# Schematic.net
KiCad netlist of a schematic drawn in EAGLE
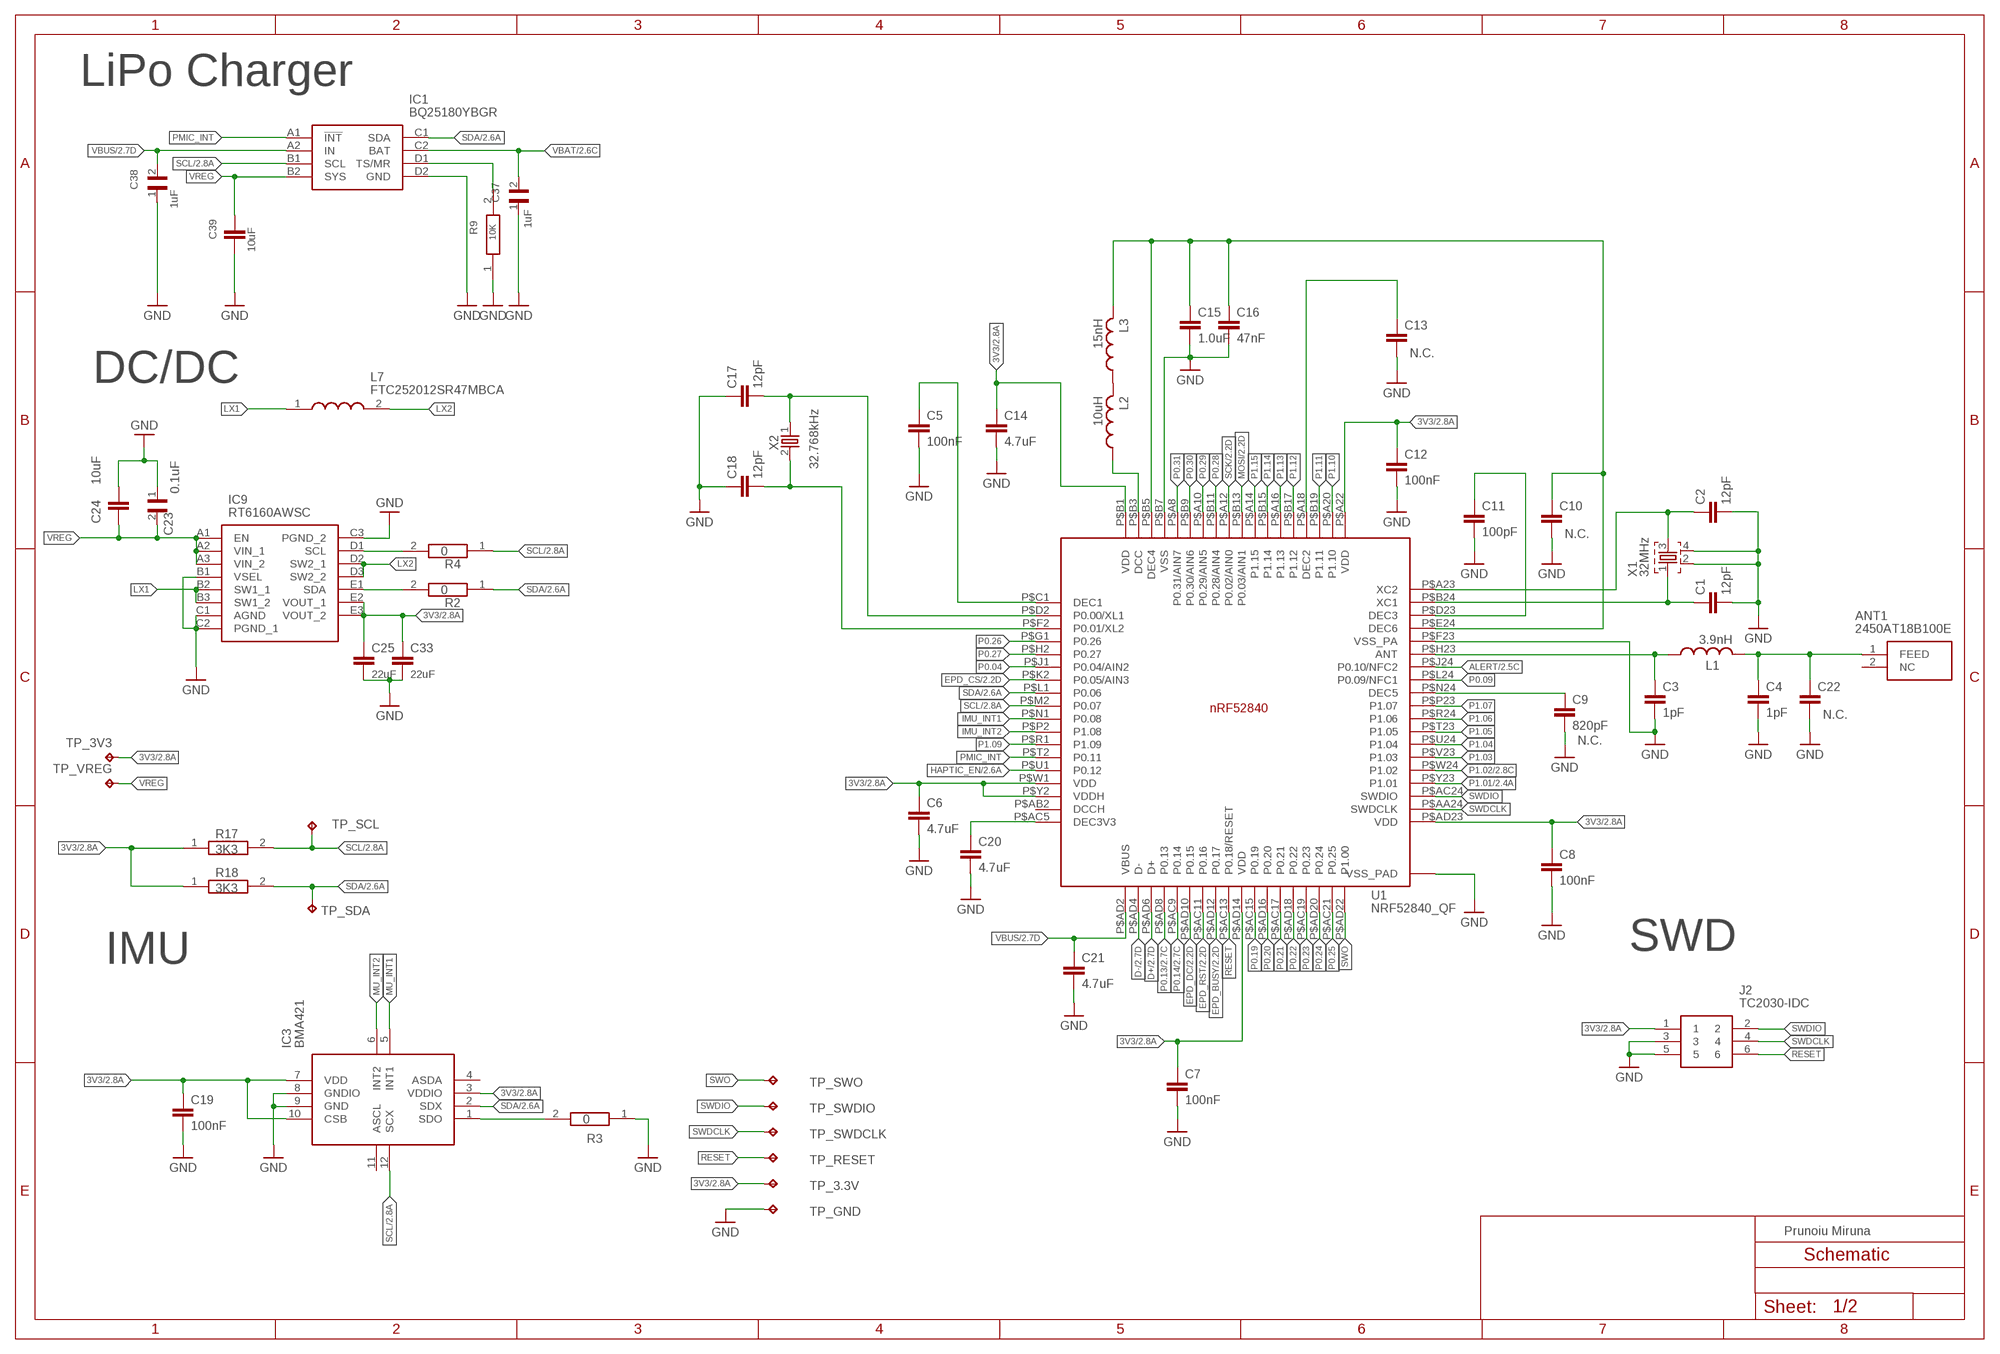
[diagram p0: schematic, sheet 1]
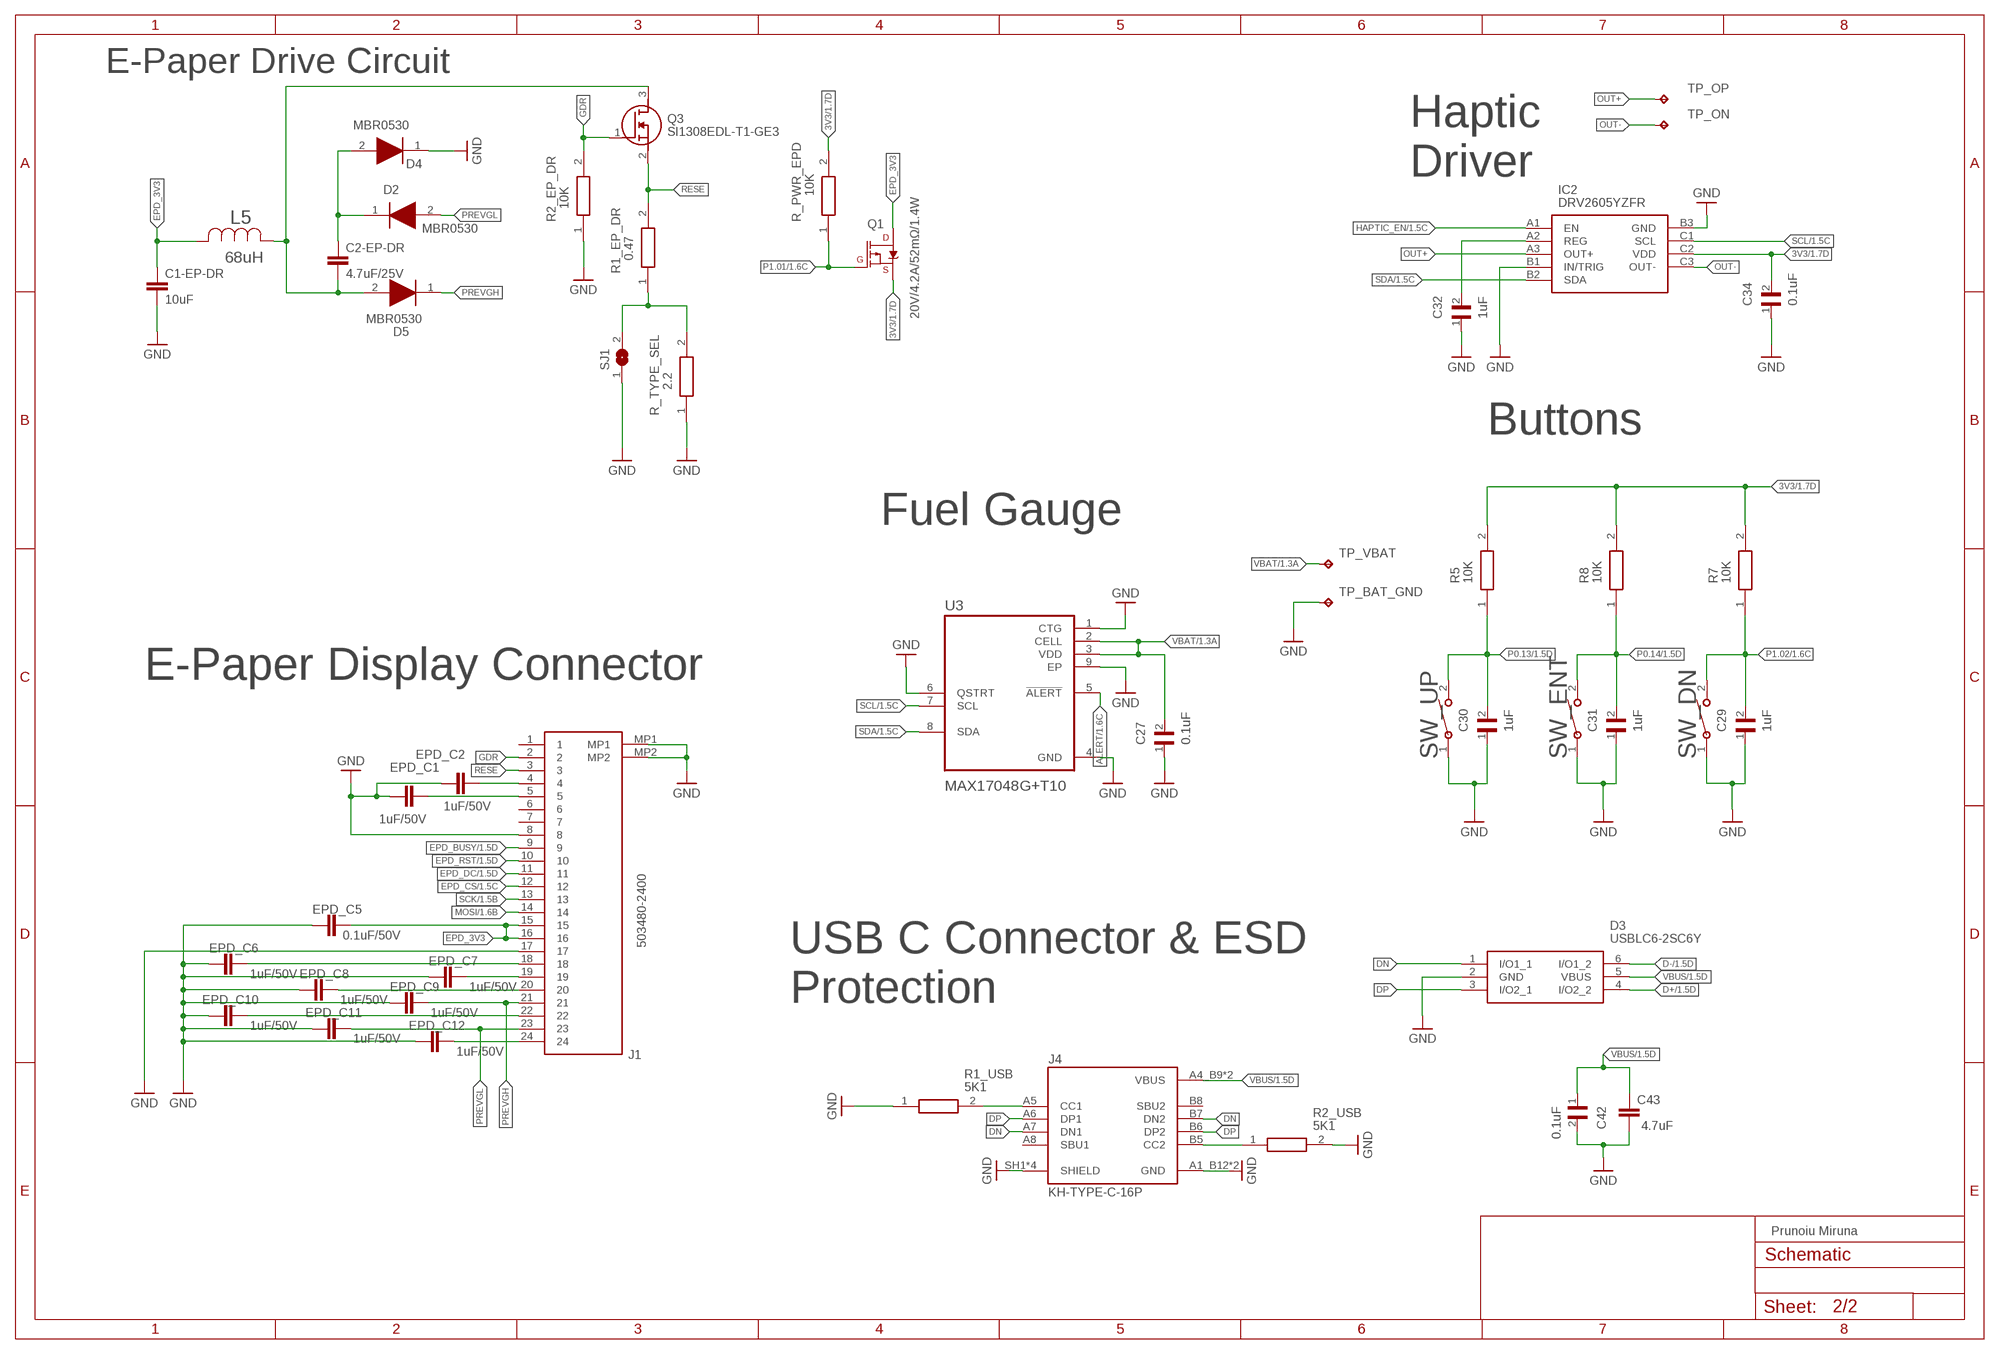
[diagram p1: schematic, sheet 2]

(export (version "E")
  (design (tool "Eeschema 10.0.6"))
  (components
    (comp (ref "C1-EP-DR")
      (value "10uF")
      (footprint "eagle-import:NORDIC_NRF_3_RESC0201_L")
      (libsource (lib "eagle-import") (part "InkTime_v5_vf.CHkS0jDyTK2MUtA_sH1VBA_NORDIC_NRF_3_CAPACITOR_0201_L"))
    )
    (comp (ref "C2-EP-DR")
      (value "4.7uF/25V")
      (footprint "eagle-import:NORDIC_NRF_3_RESC0201_L")
      (libsource (lib "eagle-import") (part "InkTime_v5_vf.CHkS0jDyTK2MUtA_sH1VBA_NORDIC_NRF_3_CAPACITOR_0201_L"))
    )
    (comp (ref "C27")
      (value "0.1uF")
      (footprint "eagle-import:GRM011R60J152KE01L_2_CAPC0201X13N")
      (fields (field (name "MF") "Murata") (field (name "MP") "GRM011R60J152KE01L"))
      (libsource (lib "eagle-import") (part "GRM011R60J152KE01L_2_GRM011R60J152KE01L"))
    )
    (comp (ref "C29")
      (value "1uF")
      (footprint "eagle-import:GRM011R60J152KE01L_2_CAPC0201X13N")
      (fields (field (name "MF") "Murata") (field (name "MP") "GRM011R60J152KE01L"))
      (libsource (lib "eagle-import") (part "GRM011R60J152KE01L_2_GRM011R60J152KE01L"))
    )
    (comp (ref "C30")
      (value "1uF")
      (footprint "eagle-import:GRM011R60J152KE01L_2_CAPC0201X13N")
      (fields (field (name "MF") "Murata") (field (name "MP") "GRM011R60J152KE01L"))
      (libsource (lib "eagle-import") (part "GRM011R60J152KE01L_2_GRM011R60J152KE01L"))
    )
    (comp (ref "C31")
      (value "1uF")
      (footprint "eagle-import:GRM011R60J152KE01L_2_CAPC0201X13N")
      (fields (field (name "MF") "Murata") (field (name "MP") "GRM011R60J152KE01L"))
      (libsource (lib "eagle-import") (part "GRM011R60J152KE01L_2_GRM011R60J152KE01L"))
    )
    (comp (ref "C32")
      (value "1uF")
      (footprint "eagle-import:GRM011R60J152KE01L_2_CAPC0201X13N")
      (fields (field (name "MF") "Murata") (field (name "MP") "GRM011R60J152KE01L"))
      (libsource (lib "eagle-import") (part "GRM011R60J152KE01L_2_GRM011R60J152KE01L"))
    )
    (comp (ref "C34")
      (value "0.1uF")
      (footprint "eagle-import:GRM011R60J152KE01L_2_CAPC0201X13N")
      (fields (field (name "MF") "Murata") (field (name "MP") "GRM011R60J152KE01L"))
      (libsource (lib "eagle-import") (part "GRM011R60J152KE01L_2_GRM011R60J152KE01L"))
    )
    (comp (ref "C42")
      (value "0.1uF")
      (footprint "eagle-import:GRM011R60J152KE01L_2_CAPC0201X13N")
      (fields (field (name "MF") "Murata") (field (name "MP") "GRM011R60J152KE01L"))
      (libsource (lib "eagle-import") (part "GRM011R60J152KE01L_2_GRM011R60J152KE01L"))
    )
    (comp (ref "C43")
      (value "4.7uF")
      (footprint "eagle-import:NORDIC_NRF_3_RESC0201_L")
      (libsource (lib "eagle-import") (part "InkTime_v5_vf.CHkS0jDyTK2MUtA_sH1VBA_NORDIC_NRF_3_CAPACITOR_0201_L"))
    )
    (comp (ref "D2")
      (value "MBR0530")
      (footprint "eagle-import:ESP32_C6_LIBRARY_5_SOD3716X135N")
      (fields (field (name "MF") "ON Semiconductor"))
      (libsource (lib "eagle-import") (part "ESP32_C6_LIBRARY_5_MBR0530"))
    )
    (comp (ref "D3")
      (value "USBLC6-2SC6Y")
      (footprint "eagle-import:ESP32_C6_LIBRARY_3_SOT95P280X145-6N")
      (fields (field (name "MF") "STMicroelectronics"))
      (libsource (lib "eagle-import") (part "ESP32_C6_LIBRARY_3_USBLC6-2SC6Y"))
    )
    (comp (ref "D4")
      (value "MBR0530")
      (footprint "eagle-import:ESP32_C6_LIBRARY_5_SOD3716X135N")
      (fields (field (name "MF") "ON Semiconductor"))
      (libsource (lib "eagle-import") (part "ESP32_C6_LIBRARY_5_MBR0530"))
    )
    (comp (ref "D5")
      (value "MBR0530")
      (footprint "eagle-import:ESP32_C6_LIBRARY_5_SOD3716X135N")
      (fields (field (name "MF") "ON Semiconductor"))
      (libsource (lib "eagle-import") (part "ESP32_C6_LIBRARY_5_MBR0530"))
    )
    (comp (ref "EPD_C1")
      (value "1uF/50V")
      (footprint "eagle-import:NORDIC_NRF_3_RESC0201_L")
      (libsource (lib "eagle-import") (part "InkTime_v5_vf.CHkS0jDyTK2MUtA_sH1VBA_NORDIC_NRF_3_CAPACITOR_0201_L"))
    )
    (comp (ref "EPD_C2")
      (value "1uF/50V")
      (footprint "eagle-import:NORDIC_NRF_3_RESC0201_L")
      (libsource (lib "eagle-import") (part "InkTime_v5_vf.CHkS0jDyTK2MUtA_sH1VBA_NORDIC_NRF_3_CAPACITOR_0201_L"))
    )
    (comp (ref "EPD_C5")
      (value "0.1uF/50V")
      (footprint "eagle-import:NORDIC_NRF_3_RESC0201_L")
      (libsource (lib "eagle-import") (part "InkTime_v5_vf.CHkS0jDyTK2MUtA_sH1VBA_NORDIC_NRF_3_CAPACITOR_0201_L"))
    )
    (comp (ref "EPD_C6")
      (value "1uF/50V")
      (footprint "eagle-import:NORDIC_NRF_3_RESC0201_L")
      (libsource (lib "eagle-import") (part "InkTime_v5_vf.CHkS0jDyTK2MUtA_sH1VBA_NORDIC_NRF_3_CAPACITOR_0201_L"))
    )
    (comp (ref "EPD_C7")
      (value "1uF/50V")
      (footprint "eagle-import:NORDIC_NRF_3_RESC0201_L")
      (libsource (lib "eagle-import") (part "InkTime_v5_vf.CHkS0jDyTK2MUtA_sH1VBA_NORDIC_NRF_3_CAPACITOR_0201_L"))
    )
    (comp (ref "EPD_C8")
      (value "1uF/50V")
      (footprint "eagle-import:NORDIC_NRF_3_RESC0201_L")
      (libsource (lib "eagle-import") (part "InkTime_v5_vf.CHkS0jDyTK2MUtA_sH1VBA_NORDIC_NRF_3_CAPACITOR_0201_L"))
    )
    (comp (ref "EPD_C9")
      (value "1uF/50V")
      (footprint "eagle-import:NORDIC_NRF_3_RESC0201_L")
      (libsource (lib "eagle-import") (part "InkTime_v5_vf.CHkS0jDyTK2MUtA_sH1VBA_NORDIC_NRF_3_CAPACITOR_0201_L"))
    )
    (comp (ref "EPD_C10")
      (value "1uF/50V")
      (footprint "eagle-import:NORDIC_NRF_3_RESC0201_L")
      (libsource (lib "eagle-import") (part "InkTime_v5_vf.CHkS0jDyTK2MUtA_sH1VBA_NORDIC_NRF_3_CAPACITOR_0201_L"))
    )
    (comp (ref "EPD_C11")
      (value "1uF/50V")
      (footprint "eagle-import:NORDIC_NRF_3_RESC0201_L")
      (libsource (lib "eagle-import") (part "InkTime_v5_vf.CHkS0jDyTK2MUtA_sH1VBA_NORDIC_NRF_3_CAPACITOR_0201_L"))
    )
    (comp (ref "EPD_C12")
      (value "1uF/50V")
      (footprint "eagle-import:NORDIC_NRF_3_RESC0201_L")
      (libsource (lib "eagle-import") (part "InkTime_v5_vf.CHkS0jDyTK2MUtA_sH1VBA_NORDIC_NRF_3_CAPACITOR_0201_L"))
    )
    (comp (ref "IC2")
      (value "DRV2605YZFR")
      (footprint "eagle-import:DRV2605YZFR_BGA9C50P3X3_144X144X62")
      (libsource (lib "eagle-import") (part "DRV2605YZFR_DRV2605YZFR"))
    )
    (comp (ref "J1")
      (value "503480-2400")
      (footprint "eagle-import:503480-2400_5034802400")
      (fields (field (name "MOUSER_PART_NUMBER") "538-503480-2400"))
      (libsource (lib "eagle-import") (part "503480-2400_503480-2400"))
    )
    (comp (ref "J4")
      (value "KH-TYPE-C-16P")
      (footprint "eagle-import:KH-TYPE-C-16P_KINGHELM_KH-TYPE-C-16P")
      (fields (field (name "MF") "kinghelm"))
      (libsource (lib "eagle-import") (part "KH-TYPE-C-16P_KH-TYPE-C-16P"))
    )
    (comp (ref "L5")
      (value "68uH")
      (footprint "eagle-import:ESP32_C6_LIBRARY_2_IND_4828-WE-TPC_WRE")
      (fields
        (field (name "MANUFACTURER_PART_NUMBER") "744043680")
        (field (name "COPYRIGHT") "Copyright (C) 2024 Ultra Librarian. All rights reserved.")
      )
      (libsource (lib "eagle-import") (part "ESP32_C6_LIBRARY_2_744043680IND_4828-WE-TPC_WRE"))
    )
    (comp (ref "Q1")
      (value "20V/4.2A/52mΩ/1.4W")
      (footprint "eagle-import:ESP32_C6_LIBRARY_4_ESP32_C6_LIBRARY_4_ESP32_C6_LIBRARY_4_ESP32_C6_LIBRARY_4_ESP32_WROVER_SPARKFUN-DISCRETESEMI_SOT23-3")
      (libsource (lib "eagle-import") (part "ESP32_C6_LIBRARY_4_ESP32_WROVER_SPARKFUN-DISCRETESEMI_MOSFET_PCH-DMG2305UX-7"))
    )
    (comp (ref "Q3")
      (value "SI1308EDL-T1-GE3")
      (footprint "eagle-import:ESP32_C6_LIBRARY_6_SOT65P210X110-3N")
      (fields (field (name "MF") "Vishay Siliconix"))
      (libsource (lib "eagle-import") (part "ESP32_C6_LIBRARY_6_SI1308EDL-T1-GE3"))
    )
    (comp (ref "R1_EP_DR")
      (value "0.47")
      (footprint "eagle-import:CPF0201D7K68C1_0201")
      (libsource (lib "eagle-import") (part "InkTime_v5_vf.CHkS0jDyTK2MUtA_sH1VBA_CPF0201D7K68C1_CPF0201D7K68C1"))
    )
    (comp (ref "R1_USB")
      (value "5K1")
      (footprint "eagle-import:CPF0201D7K68C1_0201")
      (libsource (lib "eagle-import") (part "InkTime_v5_vf.CHkS0jDyTK2MUtA_sH1VBA_CPF0201D7K68C1_CPF0201D7K68C1"))
    )
    (comp (ref "R2_EP_DR")
      (value "10K")
      (footprint "eagle-import:CPF0201D7K68C1_0201")
      (libsource (lib "eagle-import") (part "InkTime_v5_vf.CHkS0jDyTK2MUtA_sH1VBA_CPF0201D7K68C1_CPF0201D7K68C1"))
    )
    (comp (ref "R2_USB")
      (value "5K1")
      (footprint "eagle-import:CPF0201D7K68C1_0201")
      (libsource (lib "eagle-import") (part "InkTime_v5_vf.CHkS0jDyTK2MUtA_sH1VBA_CPF0201D7K68C1_CPF0201D7K68C1"))
    )
    (comp (ref "R5")
      (value "10K")
      (footprint "eagle-import:CPF0201D7K68C1_0201")
      (libsource (lib "eagle-import") (part "InkTime_v5_vf.CHkS0jDyTK2MUtA_sH1VBA_CPF0201D7K68C1_CPF0201D7K68C1"))
    )
    (comp (ref "R7")
      (value "10K")
      (footprint "eagle-import:CPF0201D7K68C1_0201")
      (libsource (lib "eagle-import") (part "InkTime_v5_vf.CHkS0jDyTK2MUtA_sH1VBA_CPF0201D7K68C1_CPF0201D7K68C1"))
    )
    (comp (ref "R8")
      (value "10K")
      (footprint "eagle-import:CPF0201D7K68C1_0201")
      (libsource (lib "eagle-import") (part "InkTime_v5_vf.CHkS0jDyTK2MUtA_sH1VBA_CPF0201D7K68C1_CPF0201D7K68C1"))
    )
    (comp (ref "R_PWR_EPD")
      (value "10K")
      (footprint "eagle-import:CPF0201D7K68C1_0201")
      (libsource (lib "eagle-import") (part "InkTime_v5_vf.CHkS0jDyTK2MUtA_sH1VBA_CPF0201D7K68C1_CPF0201D7K68C1"))
    )
    (comp (ref "R_TYPE_SEL")
      (value "2.2")
      (footprint "eagle-import:CPF0201D7K68C1_0201")
      (libsource (lib "eagle-import") (part "InkTime_v5_vf.CHkS0jDyTK2MUtA_sH1VBA_CPF0201D7K68C1_CPF0201D7K68C1"))
    )
    (comp (ref "SJ1")
      (value "ESP32_C6_LIBRARY_7_JUMPER_SJ")
      (footprint "eagle-import:ESP32_C6_LIBRARY_7_JUMPER_SJ")
      (libsource (lib "eagle-import") (part "ESP32_C6_LIBRARY_7_JUMPER_SJ"))
    )
    (comp (ref "SW_DN")
      (value "2025-10-22_07-23-44_LIBRARY_EVP-AKE31ASW_EVP-AKE31A_PAN")
      (footprint "eagle-import:2025-10-22_07-23-44_LIBRARY_SW_EVP-AKE31A_PAN")
      (fields
        (field (name "MANUFACTURER_PART_NUMBER") "EVP-AKE31A")
        (field (name "COPYRIGHT") "Copyright (C) 2025 Ultra Librarian. All rights reserved.")
      )
      (libsource (lib "eagle-import") (part "2025-10-22_07-23-44_LIBRARY_EVP-AKE31ASW_EVP-AKE31A_PAN"))
    )
    (comp (ref "SW_ENT")
      (value "2025-10-22_07-23-44_LIBRARY_EVP-AKE31ASW_EVP-AKE31A_PAN")
      (footprint "eagle-import:2025-10-22_07-23-44_LIBRARY_SW_EVP-AKE31A_PAN")
      (fields
        (field (name "MANUFACTURER_PART_NUMBER") "EVP-AKE31A")
        (field (name "COPYRIGHT") "Copyright (C) 2025 Ultra Librarian. All rights reserved.")
      )
      (libsource (lib "eagle-import") (part "2025-10-22_07-23-44_LIBRARY_EVP-AKE31ASW_EVP-AKE31A_PAN"))
    )
    (comp (ref "SW_UP")
      (value "2025-10-22_07-23-44_LIBRARY_EVP-AKE31ASW_EVP-AKE31A_PAN")
      (footprint "eagle-import:2025-10-22_07-23-44_LIBRARY_SW_EVP-AKE31A_PAN")
      (fields
        (field (name "MANUFACTURER_PART_NUMBER") "EVP-AKE31A")
        (field (name "COPYRIGHT") "Copyright (C) 2025 Ultra Librarian. All rights reserved.")
      )
      (libsource (lib "eagle-import") (part "2025-10-22_07-23-44_LIBRARY_EVP-AKE31ASW_EVP-AKE31A_PAN"))
    )
    (comp (ref "TP_BAT_GND")
      (value "HECTOR_WATCH_1_TPTP20R")
      (footprint "eagle-import:HECTOR_WATCH_1_TP20R")
      (libsource (lib "eagle-import") (part "InkTime_v5_vf.CHkS0jDyTK2MUtA_sH1VBA_HECTOR_WATCH_1_TPTP20R"))
    )
    (comp (ref "TP_ON")
      (value "HECTOR_WATCH_1_TPTP20R")
      (footprint "eagle-import:HECTOR_WATCH_1_TP20R")
      (libsource (lib "eagle-import") (part "InkTime_v5_vf.CHkS0jDyTK2MUtA_sH1VBA_HECTOR_WATCH_1_TPTP20R"))
    )
    (comp (ref "TP_OP")
      (value "HECTOR_WATCH_1_TPTP20R")
      (footprint "eagle-import:HECTOR_WATCH_1_TP20R")
      (libsource (lib "eagle-import") (part "InkTime_v5_vf.CHkS0jDyTK2MUtA_sH1VBA_HECTOR_WATCH_1_TPTP20R"))
    )
    (comp (ref "TP_VBAT")
      (value "HECTOR_WATCH_1_TPTP20R")
      (footprint "eagle-import:HECTOR_WATCH_1_TP20R")
      (libsource (lib "eagle-import") (part "InkTime_v5_vf.CHkS0jDyTK2MUtA_sH1VBA_HECTOR_WATCH_1_TPTP20R"))
    )
    (comp (ref "U3")
      (value "MAX17048G+T10")
      (footprint "eagle-import:ESP32_C6_LIBRARY_SON50P200X200X80-9N")
      (fields (field (name "MF") "Analog Devices"))
      (libsource (lib "eagle-import") (part "ESP32_C6_LIBRARY_MAX17048G+T10"))
    )
    (comp (ref "ANT1")
      (value "2450AT18B100E")
      (footprint "eagle-import:2450AT18B100E_ANTC3216X140N")
      (fields (field (name "MOUSER_PART_NUMBER") "609-2450AT18B100E"))
      (libsource (lib "eagle-import") (part "2450AT18B100E_2450AT18B100E"))
    )
    (comp (ref "C1")
      (value "12pF")
      (footprint "eagle-import:NORDIC_NRF_3_RESC0201_L")
      (libsource (lib "eagle-import") (part "InkTime_v5_vf.CHkS0jDyTK2MUtA_sH1VBA_NORDIC_NRF_3_CAPACITOR_0201_L"))
    )
    (comp (ref "C2")
      (value "12pF")
      (footprint "eagle-import:NORDIC_NRF_3_RESC0201_L")
      (libsource (lib "eagle-import") (part "InkTime_v5_vf.CHkS0jDyTK2MUtA_sH1VBA_NORDIC_NRF_3_CAPACITOR_0201_L"))
    )
    (comp (ref "C3")
      (value "1pF")
      (footprint "eagle-import:NORDIC_NRF_3_RESC0201_L")
      (libsource (lib "eagle-import") (part "InkTime_v5_vf.CHkS0jDyTK2MUtA_sH1VBA_NORDIC_NRF_3_CAPACITOR_0201_L"))
    )
    (comp (ref "C4")
      (value "1pF")
      (footprint "eagle-import:NORDIC_NRF_3_RESC0201_L")
      (libsource (lib "eagle-import") (part "InkTime_v5_vf.CHkS0jDyTK2MUtA_sH1VBA_NORDIC_NRF_3_CAPACITOR_0201_L"))
    )
    (comp (ref "C5")
      (value "100nF")
      (footprint "eagle-import:NORDIC_NRF_3_RESC0201_L")
      (libsource (lib "eagle-import") (part "InkTime_v5_vf.CHkS0jDyTK2MUtA_sH1VBA_NORDIC_NRF_3_CAPACITOR_0201_L"))
    )
    (comp (ref "C6")
      (value "4.7uF")
      (footprint "eagle-import:NORDIC_NRF_3_RESC0201_L")
      (libsource (lib "eagle-import") (part "InkTime_v5_vf.CHkS0jDyTK2MUtA_sH1VBA_NORDIC_NRF_3_CAPACITOR_0201_L"))
    )
    (comp (ref "C7")
      (value "100nF")
      (footprint "eagle-import:NORDIC_NRF_3_RESC0201_L")
      (libsource (lib "eagle-import") (part "InkTime_v5_vf.CHkS0jDyTK2MUtA_sH1VBA_NORDIC_NRF_3_CAPACITOR_0201_L"))
    )
    (comp (ref "C8")
      (value "100nF")
      (footprint "eagle-import:NORDIC_NRF_3_RESC0201_L")
      (libsource (lib "eagle-import") (part "InkTime_v5_vf.CHkS0jDyTK2MUtA_sH1VBA_NORDIC_NRF_3_CAPACITOR_0201_L"))
    )
    (comp (ref "C9")
      (value "820pF")
      (footprint "eagle-import:NORDIC_NRF_3_RESC0201_L")
      (fields (field (name "MAXTEMP") "N.C."))
      (libsource (lib "eagle-import") (part "InkTime_v5_vf.CHkS0jDyTK2MUtA_sH1VBA_NORDIC_NRF_3_CAPACITOR_0201_L"))
    )
    (comp (ref "C10")
      (value "NORDIC_NRF_3_CAPACITOR_0201_L")
      (footprint "eagle-import:NORDIC_NRF_3_RESC0201_L")
      (fields (field (name "MAXTEMP") "N.C."))
      (libsource (lib "eagle-import") (part "InkTime_v5_vf.CHkS0jDyTK2MUtA_sH1VBA_NORDIC_NRF_3_CAPACITOR_0201_L"))
    )
    (comp (ref "C11")
      (value "100pF")
      (footprint "eagle-import:NORDIC_NRF_3_RESC0201_L")
      (libsource (lib "eagle-import") (part "InkTime_v5_vf.CHkS0jDyTK2MUtA_sH1VBA_NORDIC_NRF_3_CAPACITOR_0201_L"))
    )
    (comp (ref "C12")
      (value "100nF")
      (footprint "eagle-import:NORDIC_NRF_3_RESC0201_L")
      (libsource (lib "eagle-import") (part "InkTime_v5_vf.CHkS0jDyTK2MUtA_sH1VBA_NORDIC_NRF_3_CAPACITOR_0201_L"))
    )
    (comp (ref "C13")
      (value "NORDIC_NRF_3_CAPACITOR_0201_L")
      (footprint "eagle-import:NORDIC_NRF_3_RESC0201_L")
      (fields (field (name "MAXTEMP") "N.C."))
      (libsource (lib "eagle-import") (part "InkTime_v5_vf.CHkS0jDyTK2MUtA_sH1VBA_NORDIC_NRF_3_CAPACITOR_0201_L"))
    )
    (comp (ref "C14")
      (value "4.7uF")
      (footprint "eagle-import:NORDIC_NRF_3_RESC0201_L")
      (libsource (lib "eagle-import") (part "InkTime_v5_vf.CHkS0jDyTK2MUtA_sH1VBA_NORDIC_NRF_3_CAPACITOR_0201_L"))
    )
    (comp (ref "C15")
      (value "1.0uF")
      (footprint "eagle-import:NORDIC_NRF_3_RESC0201_L")
      (libsource (lib "eagle-import") (part "InkTime_v5_vf.CHkS0jDyTK2MUtA_sH1VBA_NORDIC_NRF_3_CAPACITOR_0201_L"))
    )
    (comp (ref "C16")
      (value "47nF")
      (footprint "eagle-import:NORDIC_NRF_3_RESC0201_L")
      (libsource (lib "eagle-import") (part "InkTime_v5_vf.CHkS0jDyTK2MUtA_sH1VBA_NORDIC_NRF_3_CAPACITOR_0201_L"))
    )
    (comp (ref "C17")
      (value "12pF")
      (footprint "eagle-import:NORDIC_NRF_3_RESC0201_L")
      (libsource (lib "eagle-import") (part "InkTime_v5_vf.CHkS0jDyTK2MUtA_sH1VBA_NORDIC_NRF_3_CAPACITOR_0201_L"))
    )
    (comp (ref "C18")
      (value "12pF")
      (footprint "eagle-import:NORDIC_NRF_3_RESC0201_L")
      (libsource (lib "eagle-import") (part "InkTime_v5_vf.CHkS0jDyTK2MUtA_sH1VBA_NORDIC_NRF_3_CAPACITOR_0201_L"))
    )
    (comp (ref "C19")
      (value "100nF")
      (footprint "eagle-import:NORDIC_NRF_3_RESC0201_L")
      (libsource (lib "eagle-import") (part "NORDIC_NRF_3_CAPACITOR_0201_L"))
    )
    (comp (ref "C20")
      (value "4.7uF")
      (footprint "eagle-import:NORDIC_NRF_3_RESC0201_L")
      (libsource (lib "eagle-import") (part "InkTime_v5_vf.CHkS0jDyTK2MUtA_sH1VBA_NORDIC_NRF_3_CAPACITOR_0201_L"))
    )
    (comp (ref "C21")
      (value "4.7uF")
      (footprint "eagle-import:NORDIC_NRF_3_RESC0201_L")
      (libsource (lib "eagle-import") (part "InkTime_v5_vf.CHkS0jDyTK2MUtA_sH1VBA_NORDIC_NRF_3_CAPACITOR_0201_L"))
    )
    (comp (ref "C22")
      (value "NORDIC_NRF_3_CAPACITOR_0201_L")
      (footprint "eagle-import:NORDIC_NRF_3_RESC0201_L")
      (fields (field (name "MAXTEMP") "N.C."))
      (libsource (lib "eagle-import") (part "InkTime_v5_vf.CHkS0jDyTK2MUtA_sH1VBA_NORDIC_NRF_3_CAPACITOR_0201_L"))
    )
    (comp (ref "C23")
      (value "0.1uF")
      (footprint "eagle-import:GRM011R60J152KE01L_1_0201")
      (fields (field (name "VAL") "88"))
      (libsource (lib "eagle-import") (part "GRM011R60J152KE01L_1_GRM011R60J152KE01L"))
    )
    (comp (ref "C24")
      (value "10uF")
      (footprint "eagle-import:NORDIC_NRF_3_RESC0201_L")
      (libsource (lib "eagle-import") (part "NORDIC_NRF_3_CAPACITOR_0201_L"))
    )
    (comp (ref "C25")
      (value "22uF")
      (footprint "eagle-import:NORDIC_NRF_3_RESC0201_L")
      (libsource (lib "eagle-import") (part "NORDIC_NRF_3_CAPACITOR_0201_L"))
    )
    (comp (ref "C33")
      (value "22uF")
      (footprint "eagle-import:NORDIC_NRF_3_RESC0201_L")
      (libsource (lib "eagle-import") (part "NORDIC_NRF_3_CAPACITOR_0201_L"))
    )
    (comp (ref "C37")
      (value "1uF")
      (footprint "eagle-import:GRM011R60J152KE01L_1_0201")
      (libsource (lib "eagle-import") (part "GRM011R60J152KE01L_1_GRM011R60J152KE01L"))
    )
    (comp (ref "C38")
      (value "1uF")
      (footprint "eagle-import:GRM011R60J152KE01L_1_0201")
      (libsource (lib "eagle-import") (part "GRM011R60J152KE01L_1_GRM011R60J152KE01L"))
    )
    (comp (ref "C39")
      (value "10uF")
      (footprint "eagle-import:NORDIC_NRF_3_RESC0201_L")
      (libsource (lib "eagle-import") (part "NORDIC_NRF_3_CAPACITOR_0201_L"))
    )
    (comp (ref "IC1")
      (value "BQ25180YBGR")
      (footprint "eagle-import:BQ25180YBGR_BGA8C40P2X4_100X155X50")
      (fields (field (name "MOUSER_PART_NUMBER") "595-BQ25180YBGR"))
      (libsource (lib "eagle-import") (part "BQ25180YBGR_BQ25180YBGR"))
    )
    (comp (ref "IC3")
      (value "BMA421")
      (footprint "eagle-import:BMA423_BMA423")
      (fields (field (name "ARROW_PART_NUMBER") "BMA423") (field (name "MOUSER_PART_NUMBER") "262-BMA423"))
      (libsource (lib "eagle-import") (part "BMA423_BMA423"))
    )
    (comp (ref "IC9")
      (value "RT6160AWSC")
      (footprint "eagle-import:RT6160AWSC_BGA15C40P3X5_140X230X60")
      (fields (field (name "MOUSER_PART_NUMBER") "835-RT6160AWSC"))
      (libsource (lib "eagle-import") (part "RT6160AWSC_RT6160AWSC"))
    )
    (comp (ref "J2")
      (value "TC2030-IDC")
      (footprint "eagle-import:TC2030-IDC_TC2030IDC")
      (libsource (lib "eagle-import") (part "TC2030-IDC_TC2030-IDC"))
    )
    (comp (ref "L1")
      (value "3.9nH")
      (footprint "eagle-import:NORDIC_NRF_2_RESC0402_L")
      (libsource (lib "eagle-import") (part "NORDIC_NRF_2_INDUCTOR_0402_L"))
    )
    (comp (ref "L2")
      (value "10uH")
      (footprint "eagle-import:NORDIC_NRF_2_RESC0402_L")
      (libsource (lib "eagle-import") (part "NORDIC_NRF_2_INDUCTOR_0402_L"))
    )
    (comp (ref "L3")
      (value "15nH")
      (footprint "eagle-import:NORDIC_NRF_2_RESC0402_L")
      (libsource (lib "eagle-import") (part "NORDIC_NRF_2_INDUCTOR_0402_L"))
    )
    (comp (ref "L7")
      (value "FTC252012SR47MBCA")
      (footprint "eagle-import:MLP2016SR47MT0S1_INDC2016X100N")
      (libsource (lib "eagle-import") (part "MLP2016SR47MT0S1_FTC252012SR47MBCA"))
    )
    (comp (ref "R2")
      (value "0")
      (footprint "eagle-import:CPF0201D7K68C1_0201")
      (libsource (lib "eagle-import") (part "CPF0201D7K68C1_CPF0201D7K68C1"))
    )
    (comp (ref "R3")
      (value "0")
      (footprint "eagle-import:CPF0201D7K68C1_0201")
      (libsource (lib "eagle-import") (part "CPF0201D7K68C1_CPF0201D7K68C1"))
    )
    (comp (ref "R4")
      (value "0")
      (footprint "eagle-import:CPF0201D7K68C1_0201")
      (libsource (lib "eagle-import") (part "CPF0201D7K68C1_CPF0201D7K68C1"))
    )
    (comp (ref "R9")
      (value "10K")
      (footprint "eagle-import:CPF0201D7K68C1_0201")
      (libsource (lib "eagle-import") (part "CPF0201D7K68C1_CPF0201D7K68C1"))
    )
    (comp (ref "R17")
      (value "3K3")
      (footprint "eagle-import:CPF0201D7K68C1_0201")
      (libsource (lib "eagle-import") (part "CPF0201D7K68C1_CPF0201D7K68C1"))
    )
    (comp (ref "R18")
      (value "3K3")
      (footprint "eagle-import:CPF0201D7K68C1_0201")
      (libsource (lib "eagle-import") (part "CPF0201D7K68C1_CPF0201D7K68C1"))
    )
    (comp (ref "TP_3.3V")
      (value "HECTOR_WATCH_1_TPTP20R")
      (footprint "eagle-import:HECTOR_WATCH_1_TP20R")
      (libsource (lib "eagle-import") (part "HECTOR_WATCH_1_TPTP20R"))
    )
    (comp (ref "TP_3V3")
      (value "HECTOR_WATCH_1_TPTP20R")
      (footprint "eagle-import:HECTOR_WATCH_1_TP20R")
      (libsource (lib "eagle-import") (part "HECTOR_WATCH_1_TPTP20R"))
    )
    (comp (ref "TP_GND")
      (value "HECTOR_WATCH_1_TPTP20R")
      (footprint "eagle-import:HECTOR_WATCH_1_TP20R")
      (libsource (lib "eagle-import") (part "HECTOR_WATCH_1_TPTP20R"))
    )
    (comp (ref "TP_RESET")
      (value "HECTOR_WATCH_1_TPTP20R")
      (footprint "eagle-import:HECTOR_WATCH_1_TP20R")
      (libsource (lib "eagle-import") (part "HECTOR_WATCH_1_TPTP20R"))
    )
    (comp (ref "TP_SCL")
      (value "HECTOR_WATCH_1_TPTP20R")
      (footprint "eagle-import:HECTOR_WATCH_1_TP20R")
      (libsource (lib "eagle-import") (part "HECTOR_WATCH_1_TPTP20R"))
    )
    (comp (ref "TP_SDA")
      (value "HECTOR_WATCH_1_TPTP20R")
      (footprint "eagle-import:HECTOR_WATCH_1_TP20R")
      (libsource (lib "eagle-import") (part "HECTOR_WATCH_1_TPTP20R"))
    )
    (comp (ref "TP_SWDCLK")
      (value "HECTOR_WATCH_1_TPTP20R")
      (footprint "eagle-import:HECTOR_WATCH_1_TP20R")
      (libsource (lib "eagle-import") (part "HECTOR_WATCH_1_TPTP20R"))
    )
    (comp (ref "TP_SWDIO")
      (value "HECTOR_WATCH_1_TPTP20R")
      (footprint "eagle-import:HECTOR_WATCH_1_TP20R")
      (libsource (lib "eagle-import") (part "HECTOR_WATCH_1_TPTP20R"))
    )
    (comp (ref "TP_SWO")
      (value "HECTOR_WATCH_1_TPTP20R")
      (footprint "eagle-import:HECTOR_WATCH_1_TP20R")
      (libsource (lib "eagle-import") (part "HECTOR_WATCH_1_TPTP20R"))
    )
    (comp (ref "TP_VREG")
      (value "HECTOR_WATCH_1_TPTP20R")
      (footprint "eagle-import:HECTOR_WATCH_1_TP20R")
      (libsource (lib "eagle-import") (part "HECTOR_WATCH_1_TPTP20R"))
    )
    (comp (ref "U1")
      (value "NRF52840_QF")
      (footprint "eagle-import:NORDIC_NRF_4_AQFN50P700X700X85_HS-74N")
      (libsource (lib "eagle-import") (part "NORDIC_NRF_4_NRF52840_QF"))
    )
    (comp (ref "X1")
      (value "32MHz")
      (footprint "eagle-import:NORDIC_NRF_BT-XTAL_2016_N")
      (libsource (lib "eagle-import") (part "NORDIC_NRF_XTAL_32MHZ"))
    )
    (comp (ref "X2")
      (value "32.768kHz")
      (footprint "eagle-import:NORDIC_NRF_1_XTAL_3215_N")
      (libsource (lib "eagle-import") (part "NORDIC_NRF_1_XTAL_32KHZ"))
    )
  )
  (nets
    (net (code "1") (name "3V3") (class "Default")
      (node (ref "C12") (pin "1") (pinfunction "1_1") (pintype "passive"))
      (node (ref "C14") (pin "1") (pinfunction "1_1") (pintype "passive"))
      (node (ref "C19") (pin "1") (pinfunction "1_1") (pintype "passive"))
      (node (ref "C25") (pin "1") (pinfunction "1_1") (pintype "passive"))
      (node (ref "C33") (pin "1") (pinfunction "1_1") (pintype "passive"))
      (node (ref "C34") (pin "2") (pinfunction "2_2") (pintype "passive"))
      (node (ref "C6") (pin "1") (pinfunction "1_1") (pintype "passive"))
      (node (ref "C7") (pin "1") (pinfunction "1_1") (pintype "passive"))
      (node (ref "C8") (pin "1") (pinfunction "1_1") (pintype "passive"))
      (node (ref "IC2") (pin "C2") (pinfunction "VDD_C2") (pintype "bidirectional"))
      (node (ref "IC3") (pin "10") (pinfunction "CSB_10") (pintype "bidirectional"))
      (node (ref "IC3") (pin "3") (pinfunction "VDDIO_3") (pintype "bidirectional"))
      (node (ref "IC3") (pin "7") (pinfunction "VDD_7") (pintype "bidirectional"))
      (node (ref "IC9") (pin "E2") (pinfunction "VOUT_1_E2") (pintype "bidirectional"))
      (node (ref "IC9") (pin "E3") (pinfunction "VOUT_2_E3") (pintype "bidirectional"))
      (node (ref "J2") (pin "1") (pinfunction "1_1") (pintype "bidirectional"))
      (node (ref "Q1") (pin "2") (pinfunction "S_2") (pintype "bidirectional"))
      (node (ref "R17") (pin "1") (pinfunction "1_1") (pintype "bidirectional"))
      (node (ref "R18") (pin "1") (pinfunction "1_1") (pintype "bidirectional"))
      (node (ref "R5") (pin "2") (pinfunction "2_2") (pintype "bidirectional"))
      (node (ref "R7") (pin "2") (pinfunction "2_2") (pintype "bidirectional"))
      (node (ref "R8") (pin "2") (pinfunction "2_2") (pintype "bidirectional"))
      (node (ref "R_PWR_EPD") (pin "2") (pinfunction "2_2") (pintype "bidirectional"))
      (node (ref "TP_3.3V") (pin "TP") (pinfunction "TP_TP") (pintype "input"))
      (node (ref "TP_3V3") (pin "TP") (pinfunction "TP_TP") (pintype "input"))
      (node (ref "U1") (pin "P$A22") (pinfunction "VDD_P$A22") (pintype "power_in"))
      (node (ref "U1") (pin "P$AD14") (pinfunction "VDD_P$AD14") (pintype "power_in"))
      (node (ref "U1") (pin "P$AD23") (pinfunction "VDD_P$AD23") (pintype "power_in"))
      (node (ref "U1") (pin "P$B1") (pinfunction "VDD_P$B1") (pintype "power_in"))
      (node (ref "U1") (pin "P$W1") (pinfunction "VDD_P$W1") (pintype "power_in"))
      (node (ref "U1") (pin "P$Y2") (pinfunction "VDDH_P$Y2") (pintype "power_in"))
    )
    (net (code "2") (name "ALERT") (class "Default")
      (node (ref "U1") (pin "P$J24") (pinfunction "P0.10/NFC2_P$J24") (pintype "bidirectional"))
      (node (ref "U3") (pin "5") (pinfunction "~{ALERT}_5") (pintype "output"))
    )
    (net (code "3") (name "D+") (class "Default")
      (node (ref "D3") (pin "4") (pinfunction "I/O2_2_4") (pintype "bidirectional"))
      (node (ref "U1") (pin "P$AD6") (pinfunction "D+_P$AD6") (pintype "bidirectional"))
    )
    (net (code "4") (name "D-") (class "Default")
      (node (ref "D3") (pin "6") (pinfunction "I/O1_2_6") (pintype "bidirectional"))
      (node (ref "U1") (pin "P$AD4") (pinfunction "D-_P$AD4") (pintype "bidirectional"))
    )
    (net (code "5") (name "DN") (class "Default")
      (node (ref "D3") (pin "1") (pinfunction "I/O1_1_1") (pintype "bidirectional"))
      (node (ref "J4") (pin "A7") (pinfunction "DN1_A7") (pintype "bidirectional"))
      (node (ref "J4") (pin "B7") (pinfunction "DN2_B7") (pintype "bidirectional"))
    )
    (net (code "6") (name "DP") (class "Default")
      (node (ref "D3") (pin "3") (pinfunction "I/O2_1_3") (pintype "bidirectional"))
      (node (ref "J4") (pin "A6") (pinfunction "DP1_A6") (pintype "bidirectional"))
      (node (ref "J4") (pin "B6") (pinfunction "DP2_B6") (pintype "bidirectional"))
    )
    (net (code "7") (name "EPD_3V3") (class "Default")
      (node (ref "C1-EP-DR") (pin "1") (pinfunction "1_1") (pintype "passive"))
      (node (ref "EPD_C5") (pin "2") (pinfunction "2_2") (pintype "passive"))
      (node (ref "J1") (pin "15") (pinfunction "15_15") (pintype "bidirectional"))
      (node (ref "J1") (pin "16") (pinfunction "16_16") (pintype "bidirectional"))
      (node (ref "L5") (pin "2") (pinfunction "2_2") (pintype "passive"))
      (node (ref "Q1") (pin "3") (pinfunction "D_3") (pintype "bidirectional"))
    )
    (net (code "8") (name "EPD_BUSY") (class "Default")
      (node (ref "J1") (pin "9") (pinfunction "9_9") (pintype "bidirectional"))
      (node (ref "U1") (pin "P$AD12") (pinfunction "P0.17_P$AD12") (pintype "bidirectional"))
    )
    (net (code "9") (name "EPD_CS") (class "Default")
      (node (ref "J1") (pin "12") (pinfunction "12_12") (pintype "bidirectional"))
      (node (ref "U1") (pin "P$K2") (pinfunction "P0.05/AIN3_P$K2") (pintype "bidirectional"))
    )
    (net (code "10") (name "EPD_DC") (class "Default")
      (node (ref "J1") (pin "11") (pinfunction "11_11") (pintype "bidirectional"))
      (node (ref "U1") (pin "P$AD10") (pinfunction "P0.15_P$AD10") (pintype "bidirectional"))
    )
    (net (code "11") (name "EPD_RST") (class "Default")
      (node (ref "J1") (pin "10") (pinfunction "10_10") (pintype "bidirectional"))
      (node (ref "U1") (pin "P$AC11") (pinfunction "P0.16_P$AC11") (pintype "bidirectional"))
    )
    (net (code "12") (name "GDR") (class "Default")
      (node (ref "J1") (pin "2") (pinfunction "2_2") (pintype "bidirectional"))
      (node (ref "Q3") (pin "1") (pinfunction "G_1") (pintype "bidirectional"))
      (node (ref "R2_EP_DR") (pin "2") (pinfunction "2_2") (pintype "bidirectional"))
    )
    (net (code "13") (name "GND") (class "Default")
      (node (ref "C1") (pin "2") (pinfunction "2_2") (pintype "passive"))
      (node (ref "C1-EP-DR") (pin "2") (pinfunction "2_2") (pintype "passive"))
      (node (ref "C10") (pin "2") (pinfunction "2_2") (pintype "passive"))
      (node (ref "C11") (pin "2") (pinfunction "2_2") (pintype "passive"))
      (node (ref "C12") (pin "2") (pinfunction "2_2") (pintype "passive"))
      (node (ref "C13") (pin "2") (pinfunction "2_2") (pintype "passive"))
      (node (ref "C14") (pin "2") (pinfunction "2_2") (pintype "passive"))
      (node (ref "C15") (pin "2") (pinfunction "2_2") (pintype "passive"))
      (node (ref "C16") (pin "2") (pinfunction "2_2") (pintype "passive"))
      (node (ref "C17") (pin "1") (pinfunction "1_1") (pintype "passive"))
      (node (ref "C18") (pin "1") (pinfunction "1_1") (pintype "passive"))
      (node (ref "C19") (pin "2") (pinfunction "2_2") (pintype "passive"))
      (node (ref "C2") (pin "2") (pinfunction "2_2") (pintype "passive"))
      (node (ref "C20") (pin "2") (pinfunction "2_2") (pintype "passive"))
      (node (ref "C21") (pin "2") (pinfunction "2_2") (pintype "passive"))
      (node (ref "C22") (pin "2") (pinfunction "2_2") (pintype "passive"))
      (node (ref "C23") (pin "1") (pinfunction "1_1") (pintype "passive"))
      (node (ref "C24") (pin "1") (pinfunction "1_1") (pintype "passive"))
      (node (ref "C25") (pin "2") (pinfunction "2_2") (pintype "passive"))
      (node (ref "C27") (pin "1") (pinfunction "1_1") (pintype "passive"))
      (node (ref "C29") (pin "1") (pinfunction "1_1") (pintype "passive"))
      (node (ref "C3") (pin "2") (pinfunction "2_2") (pintype "passive"))
      (node (ref "C30") (pin "1") (pinfunction "1_1") (pintype "passive"))
      (node (ref "C31") (pin "1") (pinfunction "1_1") (pintype "passive"))
      (node (ref "C32") (pin "1") (pinfunction "1_1") (pintype "passive"))
      (node (ref "C33") (pin "2") (pinfunction "2_2") (pintype "passive"))
      (node (ref "C34") (pin "1") (pinfunction "1_1") (pintype "passive"))
      (node (ref "C37") (pin "1") (pinfunction "1_1") (pintype "passive"))
      (node (ref "C38") (pin "1") (pinfunction "1_1") (pintype "passive"))
      (node (ref "C39") (pin "2") (pinfunction "2_2") (pintype "passive"))
      (node (ref "C4") (pin "2") (pinfunction "2_2") (pintype "passive"))
      (node (ref "C42") (pin "2") (pinfunction "2_2") (pintype "passive"))
      (node (ref "C43") (pin "1") (pinfunction "1_1") (pintype "passive"))
      (node (ref "C5") (pin "2") (pinfunction "2_2") (pintype "passive"))
      (node (ref "C6") (pin "2") (pinfunction "2_2") (pintype "passive"))
      (node (ref "C7") (pin "2") (pinfunction "2_2") (pintype "passive"))
      (node (ref "C8") (pin "2") (pinfunction "2_2") (pintype "passive"))
      (node (ref "C9") (pin "2") (pinfunction "2_2") (pintype "passive"))
      (node (ref "D3") (pin "2") (pinfunction "GND_2") (pintype "bidirectional"))
      (node (ref "D4") (pin "1") (pinfunction "K_1") (pintype "bidirectional"))
      (node (ref "EPD_C1") (pin "1") (pinfunction "1_1") (pintype "passive"))
      (node (ref "EPD_C10") (pin "1") (pinfunction "1_1") (pintype "passive"))
      (node (ref "EPD_C11") (pin "1") (pinfunction "1_1") (pintype "passive"))
      (node (ref "EPD_C12") (pin "1") (pinfunction "1_1") (pintype "passive"))
      (node (ref "EPD_C2") (pin "1") (pinfunction "1_1") (pintype "passive"))
      (node (ref "EPD_C5") (pin "1") (pinfunction "1_1") (pintype "passive"))
      (node (ref "EPD_C6") (pin "1") (pinfunction "1_1") (pintype "passive"))
      (node (ref "EPD_C7") (pin "1") (pinfunction "1_1") (pintype "passive"))
      (node (ref "EPD_C8") (pin "1") (pinfunction "1_1") (pintype "passive"))
      (node (ref "EPD_C9") (pin "1") (pinfunction "1_1") (pintype "passive"))
      (node (ref "IC1") (pin "D2") (pinfunction "GND_D2") (pintype "bidirectional"))
      (node (ref "IC2") (pin "B1") (pinfunction "IN/TRIG_B1") (pintype "bidirectional"))
      (node (ref "IC2") (pin "B3") (pinfunction "GND_B3") (pintype "bidirectional"))
      (node (ref "IC3") (pin "8") (pinfunction "GNDIO_8") (pintype "bidirectional"))
      (node (ref "IC3") (pin "9") (pinfunction "GND_9") (pintype "bidirectional"))
      (node (ref "IC9") (pin "B1") (pinfunction "VSEL_B1") (pintype "bidirectional"))
      (node (ref "IC9") (pin "C1") (pinfunction "AGND_C1") (pintype "bidirectional"))
      (node (ref "IC9") (pin "C2") (pinfunction "PGND_1_C2") (pintype "bidirectional"))
      (node (ref "IC9") (pin "C3") (pinfunction "PGND_2_C3") (pintype "bidirectional"))
      (node (ref "J1") (pin "17") (pinfunction "17_17") (pintype "bidirectional"))
      (node (ref "J1") (pin "8") (pinfunction "8_8") (pintype "bidirectional"))
      (node (ref "J1") (pin "MP1") (pinfunction "MP1_MP1") (pintype "bidirectional"))
      (node (ref "J1") (pin "MP2") (pinfunction "MP2_MP2") (pintype "bidirectional"))
      (node (ref "J2") (pin "3") (pinfunction "3_3") (pintype "bidirectional"))
      (node (ref "J2") (pin "5") (pinfunction "5_5") (pintype "bidirectional"))
      (node (ref "J4") (pin "A12_B1") (pinfunction "GND_A12_B1") (pintype "power_in"))
      (node (ref "J4") (pin "A1_B12") (pinfunction "GND_A1_B12") (pintype "power_in"))
      (node (ref "J4") (pin "SH1") (pinfunction "SHIELD_SH1") (pintype "passive"))
      (node (ref "J4") (pin "SH2") (pinfunction "SHIELD_SH2") (pintype "passive"))
      (node (ref "J4") (pin "SH3") (pinfunction "SHIELD_SH3") (pintype "passive"))
      (node (ref "J4") (pin "SH4") (pinfunction "SHIELD_SH4") (pintype "passive"))
      (node (ref "R1_USB") (pin "1") (pinfunction "1_1") (pintype "bidirectional"))
      (node (ref "R2_EP_DR") (pin "1") (pinfunction "1_1") (pintype "bidirectional"))
      (node (ref "R2_USB") (pin "2") (pinfunction "2_2") (pintype "bidirectional"))
      (node (ref "R3") (pin "1") (pinfunction "1_1") (pintype "bidirectional"))
      (node (ref "R9") (pin "1") (pinfunction "1_1") (pintype "bidirectional"))
      (node (ref "R_TYPE_SEL") (pin "1") (pinfunction "1_1") (pintype "bidirectional"))
      (node (ref "SJ1") (pin "1") (pinfunction "1_1") (pintype "passive"))
      (node (ref "SW_DN") (pin "1") (pinfunction "1_1") (pintype "passive"))
      (node (ref "SW_ENT") (pin "1") (pinfunction "1_1") (pintype "passive"))
      (node (ref "SW_UP") (pin "1") (pinfunction "1_1") (pintype "passive"))
      (node (ref "TP_BAT_GND") (pin "TP") (pinfunction "TP_TP") (pintype "input"))
      (node (ref "TP_GND") (pin "TP") (pinfunction "TP_TP") (pintype "input"))
      (node (ref "U1") (pin "P$74") (pinfunction "VSS_PAD_P$74") (pintype "bidirectional"))
      (node (ref "U1") (pin "P$75") (pinfunction "VSS_PAD_P$75") (pintype "bidirectional"))
      (node (ref "U1") (pin "P$76") (pinfunction "VSS_PAD_P$76") (pintype "bidirectional"))
      (node (ref "U1") (pin "P$77") (pinfunction "VSS_PAD_P$77") (pintype "bidirectional"))
      (node (ref "U1") (pin "P$78") (pinfunction "VSS_PAD_P$78") (pintype "bidirectional"))
      (node (ref "U1") (pin "P$79") (pinfunction "VSS_PAD_P$79") (pintype "bidirectional"))
      (node (ref "U1") (pin "P$80") (pinfunction "VSS_PAD_P$80") (pintype "bidirectional"))
      (node (ref "U1") (pin "P$81") (pinfunction "VSS_PAD_P$81") (pintype "bidirectional"))
      (node (ref "U1") (pin "P$82") (pinfunction "VSS_PAD_P$82") (pintype "bidirectional"))
      (node (ref "U1") (pin "P$83") (pinfunction "VSS_PAD_P$83") (pintype "bidirectional"))
      (node (ref "U1") (pin "P$84") (pinfunction "VSS_PAD_P$84") (pintype "bidirectional"))
      (node (ref "U1") (pin "P$85") (pinfunction "VSS_PAD_P$85") (pintype "bidirectional"))
      (node (ref "U1") (pin "P$86") (pinfunction "VSS_PAD_P$86") (pintype "bidirectional"))
      (node (ref "U1") (pin "P$87") (pinfunction "VSS_PAD_P$87") (pintype "bidirectional"))
      (node (ref "U1") (pin "P$88") (pinfunction "VSS_PAD_P$88") (pintype "bidirectional"))
      (node (ref "U1") (pin "P$89") (pinfunction "VSS_PAD_P$89") (pintype "bidirectional"))
      (node (ref "U1") (pin "P$90") (pinfunction "VSS_PAD_P$90") (pintype "bidirectional"))
      (node (ref "U1") (pin "P$B7") (pinfunction "VSS_P$B7") (pintype "power_in"))
      (node (ref "U1") (pin "P$F23") (pinfunction "VSS_PA_P$F23") (pintype "bidirectional"))
      (node (ref "U3") (pin "1") (pinfunction "CTG_1") (pintype "power_in"))
      (node (ref "U3") (pin "4") (pinfunction "GND_4") (pintype "power_in"))
      (node (ref "U3") (pin "6") (pinfunction "QSTRT_6") (pintype "input"))
      (node (ref "U3") (pin "9") (pinfunction "EP_9") (pintype "power_in"))
      (node (ref "X1") (pin "2") (pinfunction "2_2") (pintype "passive"))
      (node (ref "X1") (pin "4") (pinfunction "4_4") (pintype "passive"))
    )
    (net (code "14") (name "HAPTIC_EN") (class "Default")
      (node (ref "IC2") (pin "A1") (pinfunction "EN_A1") (pintype "bidirectional"))
      (node (ref "U1") (pin "P$U1") (pinfunction "P0.12_P$U1") (pintype "bidirectional"))
    )
    (net (code "15") (name "IMU_INT1") (class "Default")
      (node (ref "U1") (pin "P$N1") (pinfunction "P0.08_P$N1") (pintype "bidirectional"))
    )
    (net (code "16") (name "IMU_INT2") (class "Default")
      (node (ref "U1") (pin "P$P2") (pinfunction "P1.08_P$P2") (pintype "bidirectional"))
    )
    (net (code "17") (name "LX1") (class "Default")
      (node (ref "IC9") (pin "B2") (pinfunction "SW1_1_B2") (pintype "bidirectional"))
      (node (ref "IC9") (pin "B3") (pinfunction "SW1_2_B3") (pintype "bidirectional"))
      (node (ref "L7") (pin "1") (pinfunction "1_1") (pintype "bidirectional"))
    )
    (net (code "18") (name "LX2") (class "Default")
      (node (ref "IC9") (pin "D2") (pinfunction "SW2_1_D2") (pintype "bidirectional"))
      (node (ref "IC9") (pin "D3") (pinfunction "SW2_2_D3") (pintype "bidirectional"))
      (node (ref "L7") (pin "2") (pinfunction "2_2") (pintype "bidirectional"))
    )
    (net (code "19") (name "MOSI") (class "Default")
      (node (ref "J1") (pin "14") (pinfunction "14_14") (pintype "bidirectional"))
      (node (ref "U1") (pin "P$B13") (pinfunction "P0.03/AIN1_P$B13") (pintype "bidirectional"))
    )
    (net (code "20") (name "MU_INT1") (class "Default")
      (node (ref "IC3") (pin "5") (pinfunction "INT1_5") (pintype "bidirectional"))
    )
    (net (code "21") (name "MU_INT2") (class "Default")
      (node (ref "IC3") (pin "6") (pinfunction "INT2_6") (pintype "bidirectional"))
    )
    (net (code "22") (name "Net-(ANT1-FEED)") (class "Default")
      (node (ref "ANT1") (pin "1") (pinfunction "FEED_1") (pintype "input"))
      (node (ref "C22") (pin "1") (pinfunction "1_1") (pintype "passive"))
      (node (ref "C4") (pin "1") (pinfunction "1_1") (pintype "passive"))
      (node (ref "L1") (pin "2") (pinfunction "2_2") (pintype "passive"))
    )
    (net (code "23") (name "Net-(D2-K)") (class "Default")
      (node (ref "C2-EP-DR") (pin "1") (pinfunction "1_1") (pintype "passive"))
      (node (ref "D2") (pin "1") (pinfunction "K_1") (pintype "bidirectional"))
      (node (ref "D4") (pin "2") (pinfunction "A_2") (pintype "bidirectional"))
    )
    (net (code "24") (name "Net-(D5-A)") (class "Default")
      (node (ref "C2-EP-DR") (pin "2") (pinfunction "2_2") (pintype "passive"))
      (node (ref "D5") (pin "2") (pinfunction "A_2") (pintype "bidirectional"))
      (node (ref "L5") (pin "1") (pinfunction "1_1") (pintype "passive"))
      (node (ref "Q3") (pin "3") (pinfunction "D_3") (pintype "bidirectional"))
    )
    (net (code "25") (name "Net-(EPD_C1-Pad2)") (class "Default")
      (node (ref "EPD_C1") (pin "2") (pinfunction "2_2") (pintype "passive"))
      (node (ref "J1") (pin "5") (pinfunction "5_5") (pintype "bidirectional"))
    )
    (net (code "26") (name "Net-(EPD_C2-Pad2)") (class "Default")
      (node (ref "EPD_C2") (pin "2") (pinfunction "2_2") (pintype "passive"))
      (node (ref "J1") (pin "4") (pinfunction "4_4") (pintype "bidirectional"))
    )
    (net (code "27") (name "Net-(EPD_C6-Pad2)") (class "Default")
      (node (ref "EPD_C6") (pin "2") (pinfunction "2_2") (pintype "passive"))
      (node (ref "J1") (pin "18") (pinfunction "18_18") (pintype "bidirectional"))
    )
    (net (code "28") (name "Net-(EPD_C7-Pad2)") (class "Default")
      (node (ref "EPD_C7") (pin "2") (pinfunction "2_2") (pintype "passive"))
      (node (ref "J1") (pin "19") (pinfunction "19_19") (pintype "bidirectional"))
    )
    (net (code "29") (name "Net-(EPD_C8-Pad2)") (class "Default")
      (node (ref "EPD_C8") (pin "2") (pinfunction "2_2") (pintype "passive"))
      (node (ref "J1") (pin "20") (pinfunction "20_20") (pintype "bidirectional"))
    )
    (net (code "30") (name "Net-(EPD_C10-Pad2)") (class "Default")
      (node (ref "EPD_C10") (pin "2") (pinfunction "2_2") (pintype "passive"))
      (node (ref "J1") (pin "22") (pinfunction "22_22") (pintype "bidirectional"))
    )
    (net (code "31") (name "Net-(EPD_C12-Pad2)") (class "Default")
      (node (ref "EPD_C12") (pin "2") (pinfunction "2_2") (pintype "passive"))
      (node (ref "J1") (pin "24") (pinfunction "24_24") (pintype "bidirectional"))
    )
    (net (code "32") (name "Net-(IC1-TS{slash}MR)") (class "Default")
      (node (ref "IC1") (pin "D1") (pinfunction "TS/MR_D1") (pintype "bidirectional"))
      (node (ref "R9") (pin "2") (pinfunction "2_2") (pintype "bidirectional"))
    )
    (net (code "33") (name "Net-(IC2-REG)") (class "Default")
      (node (ref "C32") (pin "2") (pinfunction "2_2") (pintype "passive"))
      (node (ref "IC2") (pin "A2") (pinfunction "REG_A2") (pintype "bidirectional"))
    )
    (net (code "34") (name "Net-(IC3-SDO)") (class "Default")
      (node (ref "IC3") (pin "1") (pinfunction "SDO_1") (pintype "bidirectional"))
      (node (ref "R3") (pin "2") (pinfunction "2_2") (pintype "bidirectional"))
    )
    (net (code "35") (name "Net-(IC9-SCL)") (class "Default")
      (node (ref "IC9") (pin "D1") (pinfunction "SCL_D1") (pintype "bidirectional"))
      (node (ref "R4") (pin "2") (pinfunction "2_2") (pintype "bidirectional"))
    )
    (net (code "36") (name "Net-(IC9-SDA)") (class "Default")
      (node (ref "IC9") (pin "E1") (pinfunction "SDA_E1") (pintype "bidirectional"))
      (node (ref "R2") (pin "2") (pinfunction "2_2") (pintype "bidirectional"))
    )
    (net (code "37") (name "Net-(J4-CC1)") (class "Default")
      (node (ref "J4") (pin "A5") (pinfunction "CC1_A5") (pintype "bidirectional"))
      (node (ref "R1_USB") (pin "2") (pinfunction "2_2") (pintype "bidirectional"))
    )
    (net (code "38") (name "Net-(J4-CC2)") (class "Default")
      (node (ref "J4") (pin "B5") (pinfunction "CC2_B5") (pintype "bidirectional"))
      (node (ref "R2_USB") (pin "1") (pinfunction "1_1") (pintype "bidirectional"))
    )
    (net (code "39") (name "Net-(L2-Pad2)") (class "Default")
      (node (ref "L2") (pin "2") (pinfunction "2_2") (pintype "passive"))
      (node (ref "L3") (pin "1") (pinfunction "1_1") (pintype "passive"))
    )
    (net (code "40") (name "Net-(R1_EP_DR-Pad1)") (class "Default")
      (node (ref "R1_EP_DR") (pin "1") (pinfunction "1_1") (pintype "bidirectional"))
      (node (ref "R_TYPE_SEL") (pin "2") (pinfunction "2_2") (pintype "bidirectional"))
      (node (ref "SJ1") (pin "2") (pinfunction "2_2") (pintype "passive"))
    )
    (net (code "41") (name "Net-(U1-ANT)") (class "Default")
      (node (ref "C3") (pin "1") (pinfunction "1_1") (pintype "passive"))
      (node (ref "L1") (pin "1") (pinfunction "1_1") (pintype "passive"))
      (node (ref "U1") (pin "P$H23") (pinfunction "ANT_P$H23") (pintype "bidirectional"))
    )
    (net (code "42") (name "Net-(U1-DCC)") (class "Default")
      (node (ref "L2") (pin "1") (pinfunction "1_1") (pintype "passive"))
      (node (ref "U1") (pin "P$B3") (pinfunction "DCC_P$B3") (pintype "output"))
    )
    (net (code "43") (name "Net-(U1-DEC1)") (class "Default")
      (node (ref "C5") (pin "1") (pinfunction "1_1") (pintype "passive"))
      (node (ref "U1") (pin "P$C1") (pinfunction "DEC1_P$C1") (pintype "power_in"))
    )
    (net (code "44") (name "Net-(U1-DEC2)") (class "Default")
      (node (ref "C13") (pin "1") (pinfunction "1_1") (pintype "passive"))
      (node (ref "U1") (pin "P$A18") (pinfunction "DEC2_P$A18") (pintype "bidirectional"))
    )
    (net (code "45") (name "Net-(U1-DEC3)") (class "Default")
      (node (ref "C11") (pin "1") (pinfunction "1_1") (pintype "passive"))
      (node (ref "U1") (pin "P$D23") (pinfunction "DEC3_P$D23") (pintype "bidirectional"))
    )
    (net (code "46") (name "Net-(U1-DEC3V3)") (class "Default")
      (node (ref "C20") (pin "1") (pinfunction "1_1") (pintype "passive"))
      (node (ref "U1") (pin "P$AC5") (pinfunction "DEC3V3_P$AC5") (pintype "bidirectional"))
    )
    (net (code "47") (name "Net-(U1-DEC4)") (class "Default")
      (node (ref "C10") (pin "1") (pinfunction "1_1") (pintype "passive"))
      (node (ref "C15") (pin "1") (pinfunction "1_1") (pintype "passive"))
      (node (ref "C16") (pin "1") (pinfunction "1_1") (pintype "passive"))
      (node (ref "L3") (pin "2") (pinfunction "2_2") (pintype "passive"))
      (node (ref "U1") (pin "P$B5") (pinfunction "DEC4_P$B5") (pintype "power_in"))
      (node (ref "U1") (pin "P$E24") (pinfunction "DEC6_P$E24") (pintype "bidirectional"))
    )
    (net (code "48") (name "Net-(U1-DEC5)") (class "Default")
      (node (ref "C9") (pin "1") (pinfunction "1_1") (pintype "passive"))
      (node (ref "U1") (pin "P$N24") (pinfunction "DEC5_P$N24") (pintype "bidirectional"))
    )
    (net (code "49") (name "Net-(U1-P0.00{slash}XL1)") (class "Default")
      (node (ref "C17") (pin "2") (pinfunction "2_2") (pintype "passive"))
      (node (ref "U1") (pin "P$D2") (pinfunction "P0.00/XL1_P$D2") (pintype "bidirectional"))
      (node (ref "X2") (pin "1") (pinfunction "1_1") (pintype "passive"))
    )
    (net (code "50") (name "Net-(U1-P0.01{slash}XL2)") (class "Default")
      (node (ref "C18") (pin "2") (pinfunction "2_2") (pintype "passive"))
      (node (ref "U1") (pin "P$F2") (pinfunction "P0.01/XL2_P$F2") (pintype "bidirectional"))
      (node (ref "X2") (pin "2") (pinfunction "2_2") (pintype "passive"))
    )
    (net (code "51") (name "Net-(U1-XC1)") (class "Default")
      (node (ref "C1") (pin "1") (pinfunction "1_1") (pintype "passive"))
      (node (ref "U1") (pin "P$B24") (pinfunction "XC1_P$B24") (pintype "input"))
      (node (ref "X1") (pin "1") (pinfunction "1_1") (pintype "passive"))
    )
    (net (code "52") (name "Net-(U1-XC2)") (class "Default")
      (node (ref "C2") (pin "1") (pinfunction "1_1") (pintype "passive"))
      (node (ref "U1") (pin "P$A23") (pinfunction "XC2_P$A23") (pintype "output"))
      (node (ref "X1") (pin "3") (pinfunction "3_3") (pintype "passive"))
    )
    (net (code "53") (name "OUT+") (class "Default")
      (node (ref "IC2") (pin "A3") (pinfunction "OUT+_A3") (pintype "bidirectional"))
      (node (ref "TP_OP") (pin "TP") (pinfunction "TP_TP") (pintype "input"))
    )
    (net (code "54") (name "OUT-") (class "Default")
      (node (ref "IC2") (pin "C3") (pinfunction "OUT-_C3") (pintype "bidirectional"))
      (node (ref "TP_ON") (pin "TP") (pinfunction "TP_TP") (pintype "input"))
    )
    (net (code "55") (name "P0.04") (class "Default")
      (node (ref "U1") (pin "P$J1") (pinfunction "P0.04/AIN2_P$J1") (pintype "bidirectional"))
    )
    (net (code "56") (name "P0.09") (class "Default")
      (node (ref "U1") (pin "P$L24") (pinfunction "P0.09/NFC1_P$L24") (pintype "bidirectional"))
    )
    (net (code "57") (name "P0.13") (class "Default")
      (node (ref "C30") (pin "2") (pinfunction "2_2") (pintype "passive"))
      (node (ref "R5") (pin "1") (pinfunction "1_1") (pintype "bidirectional"))
      (node (ref "SW_UP") (pin "2") (pinfunction "2_2") (pintype "passive"))
      (node (ref "U1") (pin "P$AD8") (pinfunction "P0.13_P$AD8") (pintype "bidirectional"))
    )
    (net (code "58") (name "P0.14") (class "Default")
      (node (ref "C31") (pin "2") (pinfunction "2_2") (pintype "passive"))
      (node (ref "R8") (pin "1") (pinfunction "1_1") (pintype "bidirectional"))
      (node (ref "SW_ENT") (pin "2") (pinfunction "2_2") (pintype "passive"))
      (node (ref "U1") (pin "P$AC9") (pinfunction "P0.14_P$AC9") (pintype "bidirectional"))
    )
    (net (code "59") (name "P0.19") (class "Default")
      (node (ref "U1") (pin "P$AC15") (pinfunction "P0.19_P$AC15") (pintype "bidirectional"))
    )
    (net (code "60") (name "P0.20") (class "Default")
      (node (ref "U1") (pin "P$AD16") (pinfunction "P0.20_P$AD16") (pintype "bidirectional"))
    )
    (net (code "61") (name "P0.21") (class "Default")
      (node (ref "U1") (pin "P$AC17") (pinfunction "P0.21_P$AC17") (pintype "bidirectional"))
    )
    (net (code "62") (name "P0.22") (class "Default")
      (node (ref "U1") (pin "P$AD18") (pinfunction "P0.22_P$AD18") (pintype "bidirectional"))
    )
    (net (code "63") (name "P0.23") (class "Default")
      (node (ref "U1") (pin "P$AC19") (pinfunction "P0.23_P$AC19") (pintype "bidirectional"))
    )
    (net (code "64") (name "P0.24") (class "Default")
      (node (ref "U1") (pin "P$AD20") (pinfunction "P0.24_P$AD20") (pintype "bidirectional"))
    )
    (net (code "65") (name "P0.25") (class "Default")
      (node (ref "U1") (pin "P$AC21") (pinfunction "P0.25_P$AC21") (pintype "bidirectional"))
    )
    (net (code "66") (name "P0.26") (class "Default")
      (node (ref "U1") (pin "P$G1") (pinfunction "P0.26_P$G1") (pintype "bidirectional"))
    )
    (net (code "67") (name "P0.27") (class "Default")
      (node (ref "U1") (pin "P$H2") (pinfunction "P0.27_P$H2") (pintype "bidirectional"))
    )
    (net (code "68") (name "P0.28") (class "Default")
      (node (ref "U1") (pin "P$B11") (pinfunction "P0.28/AIN4_P$B11") (pintype "bidirectional"))
    )
    (net (code "69") (name "P0.29") (class "Default")
      (node (ref "U1") (pin "P$A10") (pinfunction "P0.29/AIN5_P$A10") (pintype "bidirectional"))
    )
    (net (code "70") (name "P0.30") (class "Default")
      (node (ref "U1") (pin "P$B9") (pinfunction "P0.30/AIN6_P$B9") (pintype "bidirectional"))
    )
    (net (code "71") (name "P0.31") (class "Default")
      (node (ref "U1") (pin "P$A8") (pinfunction "P0.31/AIN7_P$A8") (pintype "bidirectional"))
    )
    (net (code "72") (name "P1.01") (class "Default")
      (node (ref "Q1") (pin "1") (pinfunction "G_1") (pintype "bidirectional"))
      (node (ref "R_PWR_EPD") (pin "1") (pinfunction "1_1") (pintype "bidirectional"))
      (node (ref "U1") (pin "P$Y23") (pinfunction "P1.01_P$Y23") (pintype "bidirectional"))
    )
    (net (code "73") (name "P1.02") (class "Default")
      (node (ref "C29") (pin "2") (pinfunction "2_2") (pintype "passive"))
      (node (ref "R7") (pin "1") (pinfunction "1_1") (pintype "bidirectional"))
      (node (ref "SW_DN") (pin "2") (pinfunction "2_2") (pintype "passive"))
      (node (ref "U1") (pin "P$W24") (pinfunction "P1.02_P$W24") (pintype "bidirectional"))
    )
    (net (code "74") (name "P1.03") (class "Default")
      (node (ref "U1") (pin "P$V23") (pinfunction "P1.03_P$V23") (pintype "bidirectional"))
    )
    (net (code "75") (name "P1.04") (class "Default")
      (node (ref "U1") (pin "P$U24") (pinfunction "P1.04_P$U24") (pintype "bidirectional"))
    )
    (net (code "76") (name "P1.05") (class "Default")
      (node (ref "U1") (pin "P$T23") (pinfunction "P1.05_P$T23") (pintype "bidirectional"))
    )
    (net (code "77") (name "P1.06") (class "Default")
      (node (ref "U1") (pin "P$R24") (pinfunction "P1.06_P$R24") (pintype "bidirectional"))
    )
    (net (code "78") (name "P1.07") (class "Default")
      (node (ref "U1") (pin "P$P23") (pinfunction "P1.07_P$P23") (pintype "bidirectional"))
    )
    (net (code "79") (name "P1.09") (class "Default")
      (node (ref "U1") (pin "P$R1") (pinfunction "P1.09_P$R1") (pintype "bidirectional"))
    )
    (net (code "80") (name "P1.10") (class "Default")
      (node (ref "U1") (pin "P$A20") (pinfunction "P1.10_P$A20") (pintype "bidirectional"))
    )
    (net (code "81") (name "P1.11") (class "Default")
      (node (ref "U1") (pin "P$B19") (pinfunction "P1.11_P$B19") (pintype "bidirectional"))
    )
    (net (code "82") (name "P1.12") (class "Default")
      (node (ref "U1") (pin "P$B17") (pinfunction "P1.12_P$B17") (pintype "bidirectional"))
    )
    (net (code "83") (name "P1.13") (class "Default")
      (node (ref "U1") (pin "P$A16") (pinfunction "P1.13_P$A16") (pintype "bidirectional"))
    )
    (net (code "84") (name "P1.14") (class "Default")
      (node (ref "U1") (pin "P$B15") (pinfunction "P1.14_P$B15") (pintype "bidirectional"))
    )
    (net (code "85") (name "P1.15") (class "Default")
      (node (ref "U1") (pin "P$A14") (pinfunction "P1.15_P$A14") (pintype "bidirectional"))
    )
    (net (code "86") (name "PMIC_INT") (class "Default")
      (node (ref "IC1") (pin "A1") (pinfunction "~{INT}_A1") (pintype "bidirectional"))
      (node (ref "U1") (pin "P$T2") (pinfunction "P0.11_P$T2") (pintype "bidirectional"))
    )
    (net (code "87") (name "PREVGH") (class "Default")
      (node (ref "D5") (pin "1") (pinfunction "K_1") (pintype "bidirectional"))
      (node (ref "EPD_C9") (pin "2") (pinfunction "2_2") (pintype "passive"))
      (node (ref "J1") (pin "21") (pinfunction "21_21") (pintype "bidirectional"))
    )
    (net (code "88") (name "PREVGL") (class "Default")
      (node (ref "D2") (pin "2") (pinfunction "A_2") (pintype "bidirectional"))
      (node (ref "EPD_C11") (pin "2") (pinfunction "2_2") (pintype "passive"))
      (node (ref "J1") (pin "23") (pinfunction "23_23") (pintype "bidirectional"))
    )
    (net (code "89") (name "RESE") (class "Default")
      (node (ref "J1") (pin "3") (pinfunction "3_3") (pintype "bidirectional"))
      (node (ref "Q3") (pin "2") (pinfunction "S_2") (pintype "bidirectional"))
      (node (ref "R1_EP_DR") (pin "2") (pinfunction "2_2") (pintype "bidirectional"))
    )
    (net (code "90") (name "RESET") (class "Default")
      (node (ref "J2") (pin "6") (pinfunction "6_6") (pintype "bidirectional"))
      (node (ref "TP_RESET") (pin "TP") (pinfunction "TP_TP") (pintype "input"))
      (node (ref "U1") (pin "P$AC13") (pinfunction "P0.18/RESET_P$AC13") (pintype "bidirectional"))
    )
    (net (code "91") (name "SCK") (class "Default")
      (node (ref "J1") (pin "13") (pinfunction "13_13") (pintype "bidirectional"))
      (node (ref "U1") (pin "P$A12") (pinfunction "P0.02/AIN0_P$A12") (pintype "bidirectional"))
    )
    (net (code "92") (name "SCL") (class "Default")
      (node (ref "IC1") (pin "B1") (pinfunction "SCL_B1") (pintype "bidirectional"))
      (node (ref "IC2") (pin "C1") (pinfunction "SCL_C1") (pintype "bidirectional"))
      (node (ref "IC3") (pin "12") (pinfunction "SCX_12") (pintype "bidirectional"))
      (node (ref "R17") (pin "2") (pinfunction "2_2") (pintype "bidirectional"))
      (node (ref "R4") (pin "1") (pinfunction "1_1") (pintype "bidirectional"))
      (node (ref "TP_SCL") (pin "TP") (pinfunction "TP_TP") (pintype "input"))
      (node (ref "U1") (pin "P$M2") (pinfunction "P0.07_P$M2") (pintype "bidirectional"))
      (node (ref "U3") (pin "7") (pinfunction "SCL_7") (pintype "input"))
    )
    (net (code "93") (name "SDA") (class "Default")
      (node (ref "IC1") (pin "C1") (pinfunction "SDA_C1") (pintype "bidirectional"))
      (node (ref "IC2") (pin "B2") (pinfunction "SDA_B2") (pintype "bidirectional"))
      (node (ref "IC3") (pin "2") (pinfunction "SDX_2") (pintype "bidirectional"))
      (node (ref "R18") (pin "2") (pinfunction "2_2") (pintype "bidirectional"))
      (node (ref "R2") (pin "1") (pinfunction "1_1") (pintype "bidirectional"))
      (node (ref "TP_SDA") (pin "TP") (pinfunction "TP_TP") (pintype "input"))
      (node (ref "U1") (pin "P$L1") (pinfunction "P0.06_P$L1") (pintype "bidirectional"))
      (node (ref "U3") (pin "8") (pinfunction "SDA_8") (pintype "bidirectional"))
    )
    (net (code "94") (name "SWDCLK") (class "Default")
      (node (ref "J2") (pin "4") (pinfunction "4_4") (pintype "bidirectional"))
      (node (ref "TP_SWDCLK") (pin "TP") (pinfunction "TP_TP") (pintype "input"))
      (node (ref "U1") (pin "P$AA24") (pinfunction "SWDCLK_P$AA24") (pintype "input"))
    )
    (net (code "95") (name "SWDIO") (class "Default")
      (node (ref "J2") (pin "2") (pinfunction "2_2") (pintype "bidirectional"))
      (node (ref "TP_SWDIO") (pin "TP") (pinfunction "TP_TP") (pintype "input"))
      (node (ref "U1") (pin "P$AC24") (pinfunction "SWDIO_P$AC24") (pintype "bidirectional"))
    )
    (net (code "96") (name "SWO") (class "Default")
      (node (ref "TP_SWO") (pin "TP") (pinfunction "TP_TP") (pintype "input"))
      (node (ref "U1") (pin "P$AD22") (pinfunction "P1.00_P$AD22") (pintype "bidirectional"))
    )
    (net (code "97") (name "VBAT") (class "Default")
      (node (ref "C27") (pin "2") (pinfunction "2_2") (pintype "passive"))
      (node (ref "C37") (pin "2") (pinfunction "2_2") (pintype "passive"))
      (node (ref "IC1") (pin "C2") (pinfunction "BAT_C2") (pintype "bidirectional"))
      (node (ref "TP_VBAT") (pin "TP") (pinfunction "TP_TP") (pintype "input"))
      (node (ref "U3") (pin "2") (pinfunction "CELL_2") (pintype "power_in"))
      (node (ref "U3") (pin "3") (pinfunction "VDD_3") (pintype "power_in"))
    )
    (net (code "98") (name "VBUS") (class "Default")
      (node (ref "C21") (pin "1") (pinfunction "1_1") (pintype "passive"))
      (node (ref "C38") (pin "2") (pinfunction "2_2") (pintype "passive"))
      (node (ref "C42") (pin "1") (pinfunction "1_1") (pintype "passive"))
      (node (ref "C43") (pin "2") (pinfunction "2_2") (pintype "passive"))
      (node (ref "D3") (pin "5") (pinfunction "VBUS_5") (pintype "bidirectional"))
      (node (ref "IC1") (pin "A2") (pinfunction "IN_A2") (pintype "bidirectional"))
      (node (ref "J4") (pin "A4_B9") (pinfunction "VBUS_A4_B9") (pintype "power_in"))
      (node (ref "J4") (pin "A9_B4") (pinfunction "VBUS_A9_B4") (pintype "power_in"))
      (node (ref "U1") (pin "P$AD2") (pinfunction "VBUS_P$AD2") (pintype "power_in"))
    )
    (net (code "99") (name "VREG") (class "Default")
      (node (ref "C23") (pin "2") (pinfunction "2_2") (pintype "passive"))
      (node (ref "C24") (pin "2") (pinfunction "2_2") (pintype "passive"))
      (node (ref "C39") (pin "1") (pinfunction "1_1") (pintype "passive"))
      (node (ref "IC1") (pin "B2") (pinfunction "SYS_B2") (pintype "bidirectional"))
      (node (ref "IC9") (pin "A1") (pinfunction "EN_A1") (pintype "bidirectional"))
      (node (ref "IC9") (pin "A2") (pinfunction "VIN_1_A2") (pintype "bidirectional"))
      (node (ref "IC9") (pin "A3") (pinfunction "VIN_2_A3") (pintype "bidirectional"))
      (node (ref "TP_VREG") (pin "TP") (pinfunction "TP_TP") (pintype "input"))
    )
    (net (code "100") (name "unconnected-(ANT1-NC-Pad2)") (class "Default")
      (node (ref "ANT1") (pin "2") (pinfunction "NC_2") (pintype "no_connect"))
    )
    (net (code "101") (name "unconnected-(IC3-ASCL-Pad11)") (class "Default")
      (node (ref "IC3") (pin "11") (pinfunction "ASCL_11") (pintype "bidirectional"))
    )
    (net (code "102") (name "unconnected-(IC3-ASDA-Pad4)") (class "Default")
      (node (ref "IC3") (pin "4") (pinfunction "ASDA_4") (pintype "bidirectional"))
    )
    (net (code "103") (name "unconnected-(J1-Pad1)") (class "Default")
      (node (ref "J1") (pin "1") (pinfunction "1_1") (pintype "bidirectional"))
    )
    (net (code "104") (name "unconnected-(J1-Pad6)") (class "Default")
      (node (ref "J1") (pin "6") (pinfunction "6_6") (pintype "bidirectional"))
    )
    (net (code "105") (name "unconnected-(J1-Pad7)") (class "Default")
      (node (ref "J1") (pin "7") (pinfunction "7_7") (pintype "bidirectional"))
    )
    (net (code "106") (name "unconnected-(J4-SBU1-PadA8)") (class "Default")
      (node (ref "J4") (pin "A8") (pinfunction "SBU1_A8") (pintype "bidirectional"))
    )
    (net (code "107") (name "unconnected-(J4-SBU2-PadB8)") (class "Default")
      (node (ref "J4") (pin "B8") (pinfunction "SBU2_B8") (pintype "bidirectional"))
    )
    (net (code "108") (name "unconnected-(U1-DCCH-PadP$AB2)") (class "Default")
      (node (ref "U1") (pin "P$AB2") (pinfunction "DCCH_P$AB2") (pintype "bidirectional"))
    )
  )
)
